# flight_comp_v1.net
KiCad netlist of a schematic drawn in EAGLE
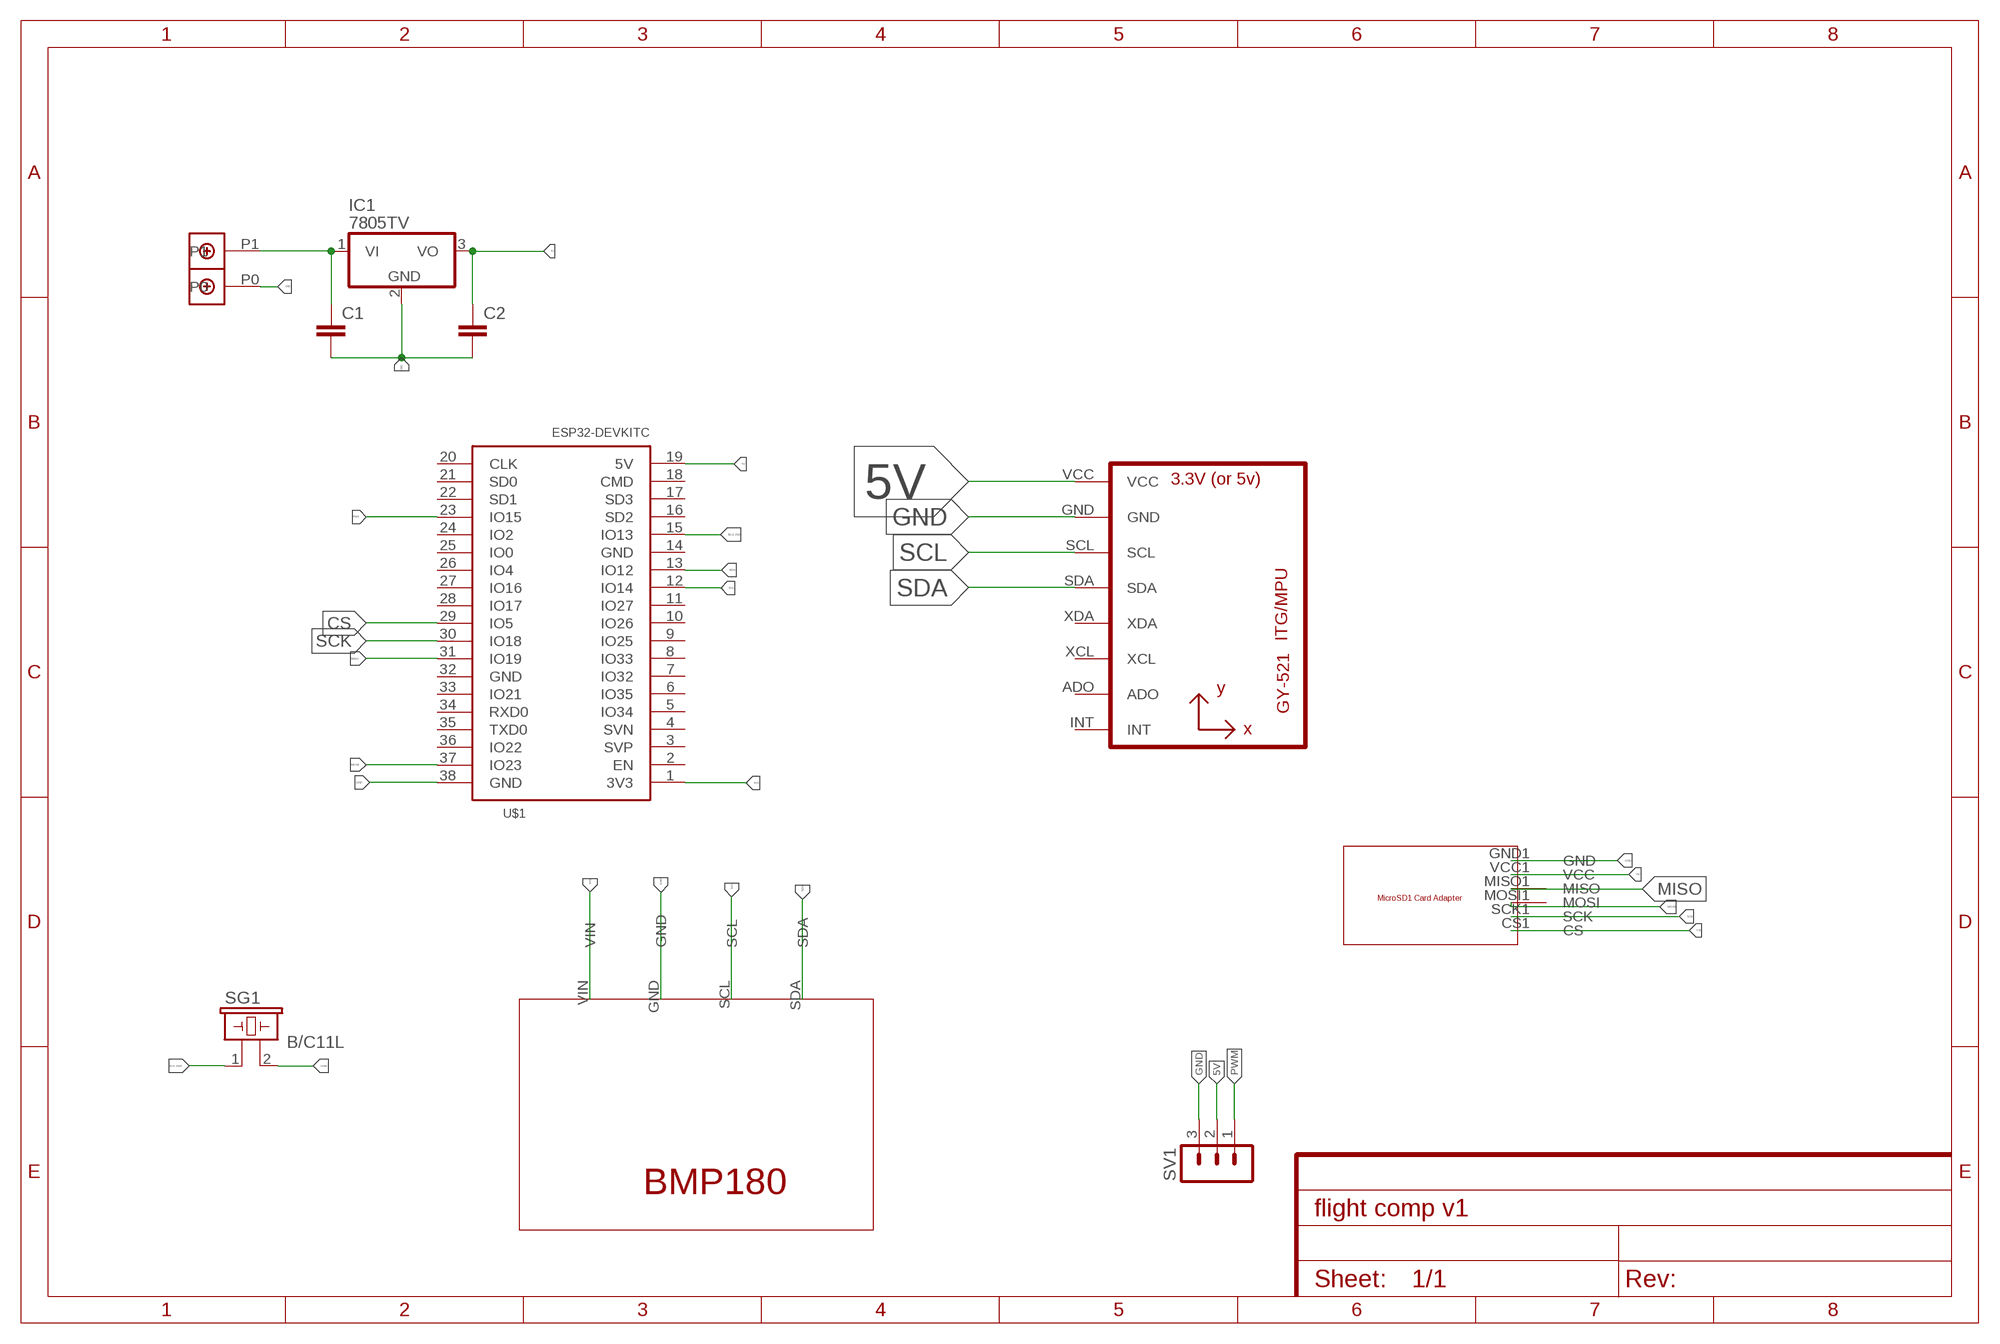
[diagram p0: schematic, sheet 1]

(export (version "E")
  (design (tool "Eeschema 10.0.6"))
  (components
    (comp (ref "C1")
      (value "C2,5-3")
      (footprint "eagle-import:C2.5-3")
      (libsource (lib "eagle-import") (part "C2,5-3"))
    )
    (comp (ref "C2")
      (value "C2,5-3")
      (footprint "eagle-import:C2.5-3")
      (libsource (lib "eagle-import") (part "C2,5-3"))
    )
    (comp (ref "IC1")
      (value "7805TV")
      (footprint "eagle-import:TO220V")
      (libsource (lib "eagle-import") (part "78TV05"))
    )
    (comp (ref "SG1")
      (value "B/C11L")
      (footprint "eagle-import:B_C11L")
      (libsource (lib "eagle-import") (part "B/C11L"))
    )
    (comp (ref "SV1")
      (value "MA03-1")
      (footprint "eagle-import:MA03-1")
      (libsource (lib "eagle-import") (part "MA03-1"))
    )
    (comp (ref "U$1")
      (value "ESP32DEVKITC")
      (footprint "eagle-import:ESP32-DEVKITC")
      (libsource (lib "eagle-import") (part "ESP32DEVKITC"))
    )
    (comp (ref "U$2")
      (value "MICROSDADAPTER")
      (footprint "eagle-import:MICROSDADAPTER")
      (libsource (lib "eagle-import") (part "MICROSDADAPTER"))
    )
    (comp (ref "U$3")
      (value "BMP180")
      (footprint "eagle-import:BMP180")
      (libsource (lib "eagle-import") (part "BMP180"))
    )
    (comp (ref "U$4")
      (value "DBCONN-1X2")
      (footprint "eagle-import:DBCONN-1X2")
      (libsource (lib "eagle-import") (part "DBCONN-1X2"))
    )
    (comp (ref "U1")
      (value "GY-521MPU6050")
      (footprint "eagle-import:GY-521")
      (libsource (lib "eagle-import") (part "GY-521MPU6050"))
    )
  )
  (nets
    (net (code "1") (name "3V3") (class "Default")
      (node (ref "U$1") (pin "1") (pinfunction "3V3_1") (pintype "bidirectional"))
      (node (ref "U$3") (pin "VIN") (pinfunction "VIN_VIN") (pintype "bidirectional"))
    )
    (net (code "2") (name "5V") (class "Default")
      (node (ref "C2") (pin "1") (pinfunction "1_1") (pintype "passive"))
      (node (ref "IC1") (pin "3") (pinfunction "VO_3") (pintype "passive"))
      (node (ref "SV1") (pin "2") (pinfunction "2_2") (pintype "passive"))
      (node (ref "U$1") (pin "19") (pinfunction "5V_19") (pintype "bidirectional"))
      (node (ref "U$2") (pin "VCC1") (pinfunction "VCC_VCC1") (pintype "bidirectional"))
      (node (ref "U1") (pin "VCC") (pinfunction "VCC_VCC") (pintype "bidirectional"))
    )
    (net (code "3") (name "BUZZER") (class "Default")
      (node (ref "SG1") (pin "1") (pinfunction "1_1") (pintype "passive"))
      (node (ref "U$1") (pin "15") (pinfunction "IO13_15") (pintype "bidirectional"))
    )
    (net (code "4") (name "CS") (class "Default")
      (node (ref "U$1") (pin "29") (pinfunction "IO5_29") (pintype "bidirectional"))
      (node (ref "U$2") (pin "CS1") (pinfunction "CS_CS1") (pintype "bidirectional"))
    )
    (net (code "5") (name "GND") (class "Default")
      (node (ref "C1") (pin "2") (pinfunction "2_2") (pintype "passive"))
      (node (ref "C2") (pin "2") (pinfunction "2_2") (pintype "passive"))
      (node (ref "IC1") (pin "2") (pinfunction "GND_2") (pintype "passive"))
      (node (ref "SG1") (pin "2") (pinfunction "2_2") (pintype "passive"))
      (node (ref "SV1") (pin "3") (pinfunction "3_3") (pintype "passive"))
      (node (ref "U$1") (pin "38") (pinfunction "GND_38") (pintype "bidirectional"))
      (node (ref "U$2") (pin "GND1") (pinfunction "GND_GND1") (pintype "bidirectional"))
      (node (ref "U$3") (pin "GND") (pinfunction "GND_GND") (pintype "bidirectional"))
      (node (ref "U$4") (pin "P0") (pinfunction "P0_P0") (pintype "bidirectional"))
      (node (ref "U1") (pin "GND") (pinfunction "GND_GND") (pintype "bidirectional"))
    )
    (net (code "6") (name "MISO") (class "Default")
      (node (ref "U$1") (pin "31") (pinfunction "IO19_31") (pintype "bidirectional"))
      (node (ref "U$2") (pin "MISO1") (pinfunction "MISO_MISO1") (pintype "bidirectional"))
    )
    (net (code "7") (name "MOSI") (class "Default")
      (node (ref "U$1") (pin "37") (pinfunction "IO23_37") (pintype "bidirectional"))
      (node (ref "U$2") (pin "MOSI1") (pinfunction "MOSI_MOSI1") (pintype "bidirectional"))
    )
    (net (code "8") (name "Net-(IC1-VI)") (class "Default")
      (node (ref "C1") (pin "1") (pinfunction "1_1") (pintype "passive"))
      (node (ref "IC1") (pin "1") (pinfunction "VI_1") (pintype "input"))
      (node (ref "U$4") (pin "P1") (pinfunction "P1_P1") (pintype "bidirectional"))
    )
    (net (code "9") (name "PWM") (class "Default")
      (node (ref "SV1") (pin "1") (pinfunction "1_1") (pintype "passive"))
      (node (ref "U$1") (pin "23") (pinfunction "IO15_23") (pintype "bidirectional"))
    )
    (net (code "10") (name "SCK") (class "Default")
      (node (ref "U$1") (pin "30") (pinfunction "IO18_30") (pintype "bidirectional"))
      (node (ref "U$2") (pin "SCK1") (pinfunction "SCK_SCK1") (pintype "bidirectional"))
    )
    (net (code "11") (name "SCL") (class "Default")
      (node (ref "U$1") (pin "12") (pinfunction "IO14_12") (pintype "bidirectional"))
      (node (ref "U$3") (pin "SCL") (pinfunction "SCL_SCL") (pintype "bidirectional"))
      (node (ref "U1") (pin "SCL") (pinfunction "SCL_SCL") (pintype "bidirectional"))
    )
    (net (code "12") (name "SDA") (class "Default")
      (node (ref "U$1") (pin "13") (pinfunction "IO12_13") (pintype "bidirectional"))
      (node (ref "U$3") (pin "SDA") (pinfunction "SDA_SDA") (pintype "bidirectional"))
      (node (ref "U1") (pin "SDA") (pinfunction "SDA_SDA") (pintype "bidirectional"))
    )
    (net (code "13") (name "unconnected-(U$1-CLK-Pad20)") (class "Default")
      (node (ref "U$1") (pin "20") (pinfunction "CLK_20") (pintype "bidirectional"))
    )
    (net (code "14") (name "unconnected-(U$1-CMD-Pad18)") (class "Default")
      (node (ref "U$1") (pin "18") (pinfunction "CMD_18") (pintype "bidirectional"))
    )
    (net (code "15") (name "unconnected-(U$1-EN-Pad2)") (class "Default")
      (node (ref "U$1") (pin "2") (pinfunction "EN_2") (pintype "bidirectional"))
    )
    (net (code "16") (name "unconnected-(U$1-GND-Pad14)") (class "Default")
      (node (ref "U$1") (pin "14") (pinfunction "GND_14") (pintype "bidirectional"))
    )
    (net (code "17") (name "unconnected-(U$1-GND-Pad32)") (class "Default")
      (node (ref "U$1") (pin "32") (pinfunction "GND_32") (pintype "bidirectional"))
    )
    (net (code "18") (name "unconnected-(U$1-IO0-Pad25)") (class "Default")
      (node (ref "U$1") (pin "25") (pinfunction "IO0_25") (pintype "bidirectional"))
    )
    (net (code "19") (name "unconnected-(U$1-IO2-Pad24)") (class "Default")
      (node (ref "U$1") (pin "24") (pinfunction "IO2_24") (pintype "bidirectional"))
    )
    (net (code "20") (name "unconnected-(U$1-IO4-Pad26)") (class "Default")
      (node (ref "U$1") (pin "26") (pinfunction "IO4_26") (pintype "bidirectional"))
    )
    (net (code "21") (name "unconnected-(U$1-IO16-Pad27)") (class "Default")
      (node (ref "U$1") (pin "27") (pinfunction "IO16_27") (pintype "bidirectional"))
    )
    (net (code "22") (name "unconnected-(U$1-IO17-Pad28)") (class "Default")
      (node (ref "U$1") (pin "28") (pinfunction "IO17_28") (pintype "bidirectional"))
    )
    (net (code "23") (name "unconnected-(U$1-IO21-Pad33)") (class "Default")
      (node (ref "U$1") (pin "33") (pinfunction "IO21_33") (pintype "bidirectional"))
    )
    (net (code "24") (name "unconnected-(U$1-IO22-Pad36)") (class "Default")
      (node (ref "U$1") (pin "36") (pinfunction "IO22_36") (pintype "bidirectional"))
    )
    (net (code "25") (name "unconnected-(U$1-IO25-Pad9)") (class "Default")
      (node (ref "U$1") (pin "9") (pinfunction "IO25_9") (pintype "bidirectional"))
    )
    (net (code "26") (name "unconnected-(U$1-IO26-Pad10)") (class "Default")
      (node (ref "U$1") (pin "10") (pinfunction "IO26_10") (pintype "bidirectional"))
    )
    (net (code "27") (name "unconnected-(U$1-IO27-Pad11)") (class "Default")
      (node (ref "U$1") (pin "11") (pinfunction "IO27_11") (pintype "bidirectional"))
    )
    (net (code "28") (name "unconnected-(U$1-IO32-Pad7)") (class "Default")
      (node (ref "U$1") (pin "7") (pinfunction "IO32_7") (pintype "bidirectional"))
    )
    (net (code "29") (name "unconnected-(U$1-IO33-Pad8)") (class "Default")
      (node (ref "U$1") (pin "8") (pinfunction "IO33_8") (pintype "bidirectional"))
    )
    (net (code "30") (name "unconnected-(U$1-IO34-Pad5)") (class "Default")
      (node (ref "U$1") (pin "5") (pinfunction "IO34_5") (pintype "bidirectional"))
    )
    (net (code "31") (name "unconnected-(U$1-IO35-Pad6)") (class "Default")
      (node (ref "U$1") (pin "6") (pinfunction "IO35_6") (pintype "bidirectional"))
    )
    (net (code "32") (name "unconnected-(U$1-RXD0-Pad34)") (class "Default")
      (node (ref "U$1") (pin "34") (pinfunction "RXD0_34") (pintype "bidirectional"))
    )
    (net (code "33") (name "unconnected-(U$1-SD0-Pad21)") (class "Default")
      (node (ref "U$1") (pin "21") (pinfunction "SD0_21") (pintype "bidirectional"))
    )
    (net (code "34") (name "unconnected-(U$1-SD1-Pad22)") (class "Default")
      (node (ref "U$1") (pin "22") (pinfunction "SD1_22") (pintype "bidirectional"))
    )
    (net (code "35") (name "unconnected-(U$1-SD2-Pad16)") (class "Default")
      (node (ref "U$1") (pin "16") (pinfunction "SD2_16") (pintype "bidirectional"))
    )
    (net (code "36") (name "unconnected-(U$1-SD3-Pad17)") (class "Default")
      (node (ref "U$1") (pin "17") (pinfunction "SD3_17") (pintype "bidirectional"))
    )
    (net (code "37") (name "unconnected-(U$1-SVN-Pad4)") (class "Default")
      (node (ref "U$1") (pin "4") (pinfunction "SVN_4") (pintype "bidirectional"))
    )
    (net (code "38") (name "unconnected-(U$1-SVP-Pad3)") (class "Default")
      (node (ref "U$1") (pin "3") (pinfunction "SVP_3") (pintype "bidirectional"))
    )
    (net (code "39") (name "unconnected-(U$1-TXD0-Pad35)") (class "Default")
      (node (ref "U$1") (pin "35") (pinfunction "TXD0_35") (pintype "bidirectional"))
    )
    (net (code "40") (name "unconnected-(U1-PadADO)") (class "Default")
      (node (ref "U1") (pin "ADO") (pinfunction "ADO_ADO") (pintype "bidirectional"))
    )
    (net (code "41") (name "unconnected-(U1-PadINT)") (class "Default")
      (node (ref "U1") (pin "INT") (pinfunction "INT_INT") (pintype "bidirectional"))
    )
    (net (code "42") (name "unconnected-(U1-PadXCL)") (class "Default")
      (node (ref "U1") (pin "XCL") (pinfunction "XCL_XCL") (pintype "bidirectional"))
    )
    (net (code "43") (name "unconnected-(U1-PadXDA)") (class "Default")
      (node (ref "U1") (pin "XDA") (pinfunction "XDA_XDA") (pintype "bidirectional"))
    )
  )
)
